# 214_oled_for_JetRacer.net
KiCad netlist of a schematic drawn in EAGLE
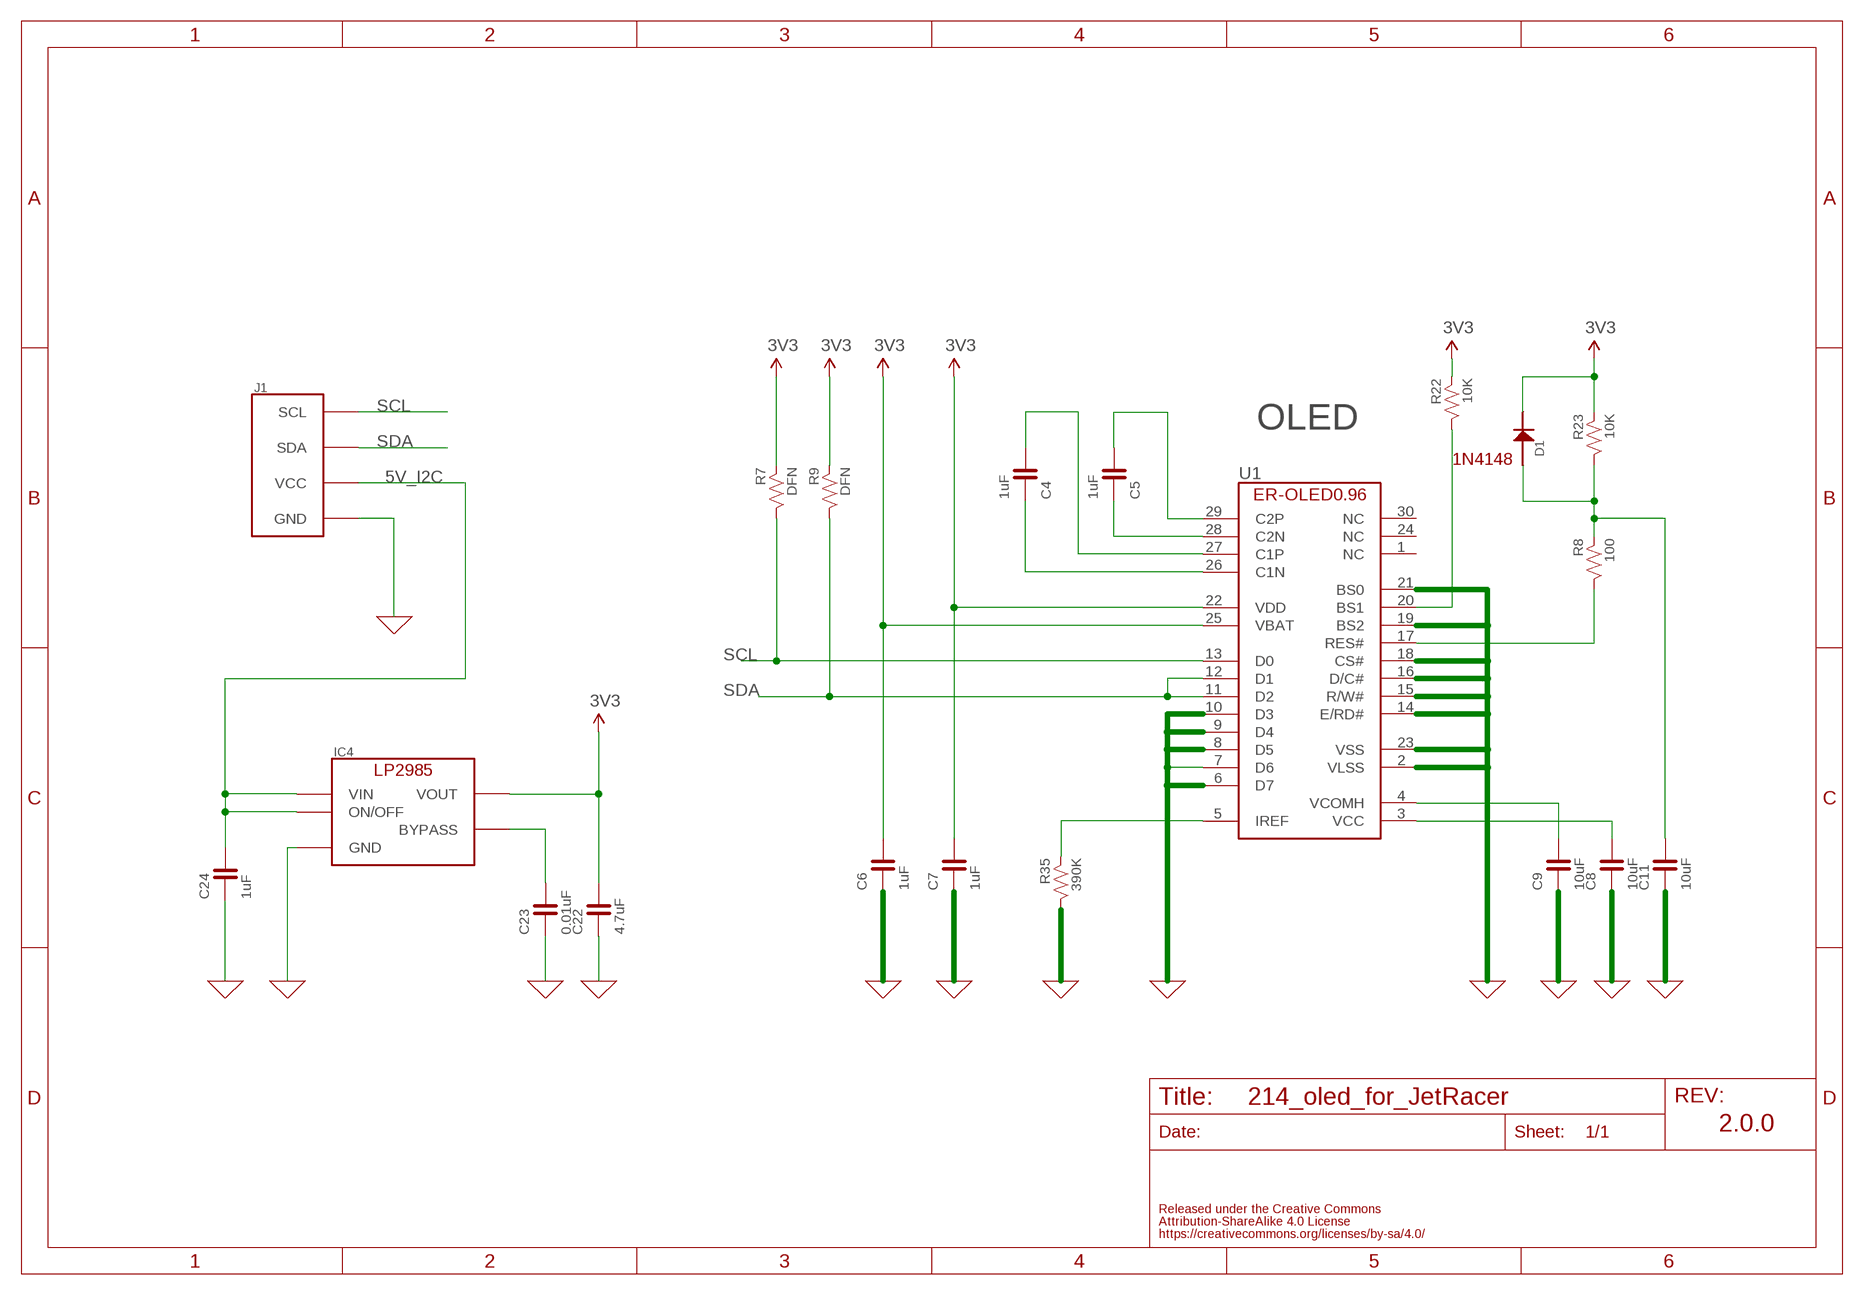
[diagram p0: schematic, sheet 1]

(export (version "E")
  (design (tool "Eeschema 10.0.6"))
  (components
    (comp (ref "C4")
      (value "1uF")
      (footprint "eagle-import:0603")
      (libsource (lib "eagle-import") (part "CAPACITOR-0603"))
    )
    (comp (ref "C5")
      (value "1uF")
      (footprint "eagle-import:0603")
      (libsource (lib "eagle-import") (part "CAPACITOR-0603"))
    )
    (comp (ref "C6")
      (value "1uF")
      (footprint "eagle-import:0603")
      (libsource (lib "eagle-import") (part "CAPACITOR-0603"))
    )
    (comp (ref "C7")
      (value "1uF")
      (footprint "eagle-import:0603")
      (libsource (lib "eagle-import") (part "CAPACITOR-0603"))
    )
    (comp (ref "C8")
      (value "10uF")
      (footprint "eagle-import:0603")
      (libsource (lib "eagle-import") (part "CAPACITOR-0603"))
    )
    (comp (ref "C9")
      (value "10uF")
      (footprint "eagle-import:0603")
      (libsource (lib "eagle-import") (part "CAPACITOR-0603"))
    )
    (comp (ref "C11")
      (value "10uF")
      (footprint "eagle-import:0603")
      (libsource (lib "eagle-import") (part "CAPACITOR-0603"))
    )
    (comp (ref "C22")
      (value "4.7uF")
      (footprint "eagle-import:0603")
      (libsource (lib "eagle-import") (part "CAPACITOR-0603"))
    )
    (comp (ref "C23")
      (value "0.01uF")
      (footprint "eagle-import:0603")
      (libsource (lib "eagle-import") (part "CAPACITOR-0603"))
    )
    (comp (ref "C24")
      (value "1uF")
      (footprint "eagle-import:0603")
      (libsource (lib "eagle-import") (part "CAPACITOR-0603"))
    )
    (comp (ref "D1")
      (value "1N4148")
      (footprint "eagle-import:1N4148W")
      (libsource (lib "eagle-import") (part "1N4148"))
    )
    (comp (ref "IC4")
      (value "LP2985-33DBV")
      (footprint "eagle-import:SOT-23-5")
      (libsource (lib "eagle-import") (part "LP2985-33DBV"))
    )
    (comp (ref "J1")
      (value "FABO_BRICK_I2C-S04B-PASK-2")
      (footprint "eagle-import:FABO_BRICK_I2C_S04B-PASK-2")
      (libsource (lib "eagle-import") (part "FABO_BRICK_I2C-S04B-PASK-2"))
    )
    (comp (ref "R7")
      (value "DFN")
      (footprint "eagle-import:0603")
      (libsource (lib "eagle-import") (part "RESISTOR-0603"))
    )
    (comp (ref "R8")
      (value "100")
      (footprint "eagle-import:0603")
      (libsource (lib "eagle-import") (part "RESISTOR-0603"))
    )
    (comp (ref "R9")
      (value "DFN")
      (footprint "eagle-import:0603")
      (libsource (lib "eagle-import") (part "RESISTOR-0603"))
    )
    (comp (ref "R22")
      (value "10K")
      (footprint "eagle-import:0603")
      (libsource (lib "eagle-import") (part "RESISTOR-0603"))
    )
    (comp (ref "R23")
      (value "10K")
      (footprint "eagle-import:0603")
      (libsource (lib "eagle-import") (part "RESISTOR-0603"))
    )
    (comp (ref "R35")
      (value "390K")
      (footprint "eagle-import:0603")
      (libsource (lib "eagle-import") (part "RESISTOR-0603"))
    )
    (comp (ref "U1")
      (value "ER-OLED0.96-1ER-CON30HT-1")
      (footprint "eagle-import:ER-CON30HT-1")
      (libsource (lib "eagle-import") (part "ER-OLED0.96-1ER-CON30HT-1"))
    )
  )
  (nets
    (net (code "1") (name "/5V_I2C") (class "Default")
      (node (ref "C24") (pin "2") (pinfunction "2_2") (pintype "passive"))
      (node (ref "IC4") (pin "1") (pinfunction "VIN_1") (pintype "input"))
      (node (ref "IC4") (pin "3") (pinfunction "ON/OFF_3") (pintype "input"))
      (node (ref "J1") (pin "VCC") (pinfunction "VCC_VCC") (pintype "bidirectional"))
    )
    (net (code "2") (name "/SCL") (class "Default")
      (node (ref "J1") (pin "SCL") (pinfunction "SCL_SCL") (pintype "bidirectional"))
      (node (ref "R7") (pin "2") (pinfunction "2_2") (pintype "bidirectional"))
      (node (ref "U1") (pin "13") (pinfunction "D0_13") (pintype "bidirectional"))
    )
    (net (code "3") (name "/SDA") (class "Default")
      (node (ref "J1") (pin "SDA") (pinfunction "SDA_SDA") (pintype "bidirectional"))
      (node (ref "R9") (pin "2") (pinfunction "2_2") (pintype "bidirectional"))
      (node (ref "U1") (pin "11") (pinfunction "D2_11") (pintype "bidirectional"))
      (node (ref "U1") (pin "12") (pinfunction "D1_12") (pintype "bidirectional"))
    )
    (net (code "4") (name "3V3") (class "Default")
      (node (ref "C22") (pin "2") (pinfunction "2_2") (pintype "passive"))
      (node (ref "C6") (pin "2") (pinfunction "2_2") (pintype "passive"))
      (node (ref "C7") (pin "2") (pinfunction "2_2") (pintype "passive"))
      (node (ref "D1") (pin "CATHODE") (pinfunction "CATHODE_CATHODE") (pintype "bidirectional"))
      (node (ref "IC4") (pin "5") (pinfunction "VOUT_5") (pintype "output"))
      (node (ref "R22") (pin "1") (pinfunction "1_1") (pintype "bidirectional"))
      (node (ref "R23") (pin "1") (pinfunction "1_1") (pintype "bidirectional"))
      (node (ref "R7") (pin "1") (pinfunction "1_1") (pintype "bidirectional"))
      (node (ref "R9") (pin "1") (pinfunction "1_1") (pintype "bidirectional"))
      (node (ref "U1") (pin "22") (pinfunction "VDD_22") (pintype "bidirectional"))
      (node (ref "U1") (pin "25") (pinfunction "VBAT_25") (pintype "bidirectional"))
    )
    (net (code "5") (name "GND") (class "Default")
      (node (ref "C11") (pin "1") (pinfunction "1_1") (pintype "passive"))
      (node (ref "C22") (pin "1") (pinfunction "1_1") (pintype "passive"))
      (node (ref "C23") (pin "1") (pinfunction "1_1") (pintype "passive"))
      (node (ref "C24") (pin "1") (pinfunction "1_1") (pintype "passive"))
      (node (ref "C6") (pin "1") (pinfunction "1_1") (pintype "passive"))
      (node (ref "C7") (pin "1") (pinfunction "1_1") (pintype "passive"))
      (node (ref "C8") (pin "1") (pinfunction "1_1") (pintype "passive"))
      (node (ref "C9") (pin "1") (pinfunction "1_1") (pintype "passive"))
      (node (ref "IC4") (pin "2") (pinfunction "GND_2") (pintype "power_in"))
      (node (ref "J1") (pin "GND") (pinfunction "GND_GND") (pintype "bidirectional"))
      (node (ref "R35") (pin "2") (pinfunction "2_2") (pintype "bidirectional"))
      (node (ref "U1") (pin "10") (pinfunction "D3_10") (pintype "bidirectional"))
      (node (ref "U1") (pin "14") (pinfunction "E/RD#_14") (pintype "bidirectional"))
      (node (ref "U1") (pin "15") (pinfunction "R/W#_15") (pintype "bidirectional"))
      (node (ref "U1") (pin "16") (pinfunction "D/C#_16") (pintype "bidirectional"))
      (node (ref "U1") (pin "18") (pinfunction "CS#_18") (pintype "bidirectional"))
      (node (ref "U1") (pin "19") (pinfunction "BS2_19") (pintype "bidirectional"))
      (node (ref "U1") (pin "2") (pinfunction "VLSS_2") (pintype "bidirectional"))
      (node (ref "U1") (pin "21") (pinfunction "BS0_21") (pintype "bidirectional"))
      (node (ref "U1") (pin "23") (pinfunction "VSS_23") (pintype "bidirectional"))
      (node (ref "U1") (pin "6") (pinfunction "D7_6") (pintype "bidirectional"))
      (node (ref "U1") (pin "7") (pinfunction "D6_7") (pintype "bidirectional"))
      (node (ref "U1") (pin "8") (pinfunction "D5_8") (pintype "bidirectional"))
      (node (ref "U1") (pin "9") (pinfunction "D4_9") (pintype "bidirectional"))
    )
    (net (code "6") (name "Net-(C11-Pad2)") (class "Default")
      (node (ref "C11") (pin "2") (pinfunction "2_2") (pintype "passive"))
      (node (ref "D1") (pin "ANODE") (pinfunction "ANODE_ANODE") (pintype "bidirectional"))
      (node (ref "R23") (pin "2") (pinfunction "2_2") (pintype "bidirectional"))
      (node (ref "R8") (pin "1") (pinfunction "1_1") (pintype "bidirectional"))
    )
    (net (code "7") (name "Net-(IC4-BYPASS)") (class "Default")
      (node (ref "C23") (pin "2") (pinfunction "2_2") (pintype "passive"))
      (node (ref "IC4") (pin "4") (pinfunction "BYPASS_4") (pintype "bidirectional"))
    )
    (net (code "8") (name "Net-(U1-BS1)") (class "Default")
      (node (ref "R22") (pin "2") (pinfunction "2_2") (pintype "bidirectional"))
      (node (ref "U1") (pin "20") (pinfunction "BS1_20") (pintype "bidirectional"))
    )
    (net (code "9") (name "Net-(U1-C1N)") (class "Default")
      (node (ref "C4") (pin "1") (pinfunction "1_1") (pintype "passive"))
      (node (ref "U1") (pin "26") (pinfunction "C1N_26") (pintype "bidirectional"))
    )
    (net (code "10") (name "Net-(U1-C1P)") (class "Default")
      (node (ref "C4") (pin "2") (pinfunction "2_2") (pintype "passive"))
      (node (ref "U1") (pin "27") (pinfunction "C1P_27") (pintype "bidirectional"))
    )
    (net (code "11") (name "Net-(U1-C2N)") (class "Default")
      (node (ref "C5") (pin "1") (pinfunction "1_1") (pintype "passive"))
      (node (ref "U1") (pin "28") (pinfunction "C2N_28") (pintype "bidirectional"))
    )
    (net (code "12") (name "Net-(U1-C2P)") (class "Default")
      (node (ref "C5") (pin "2") (pinfunction "2_2") (pintype "passive"))
      (node (ref "U1") (pin "29") (pinfunction "C2P_29") (pintype "bidirectional"))
    )
    (net (code "13") (name "Net-(U1-IREF)") (class "Default")
      (node (ref "R35") (pin "1") (pinfunction "1_1") (pintype "bidirectional"))
      (node (ref "U1") (pin "5") (pinfunction "IREF_5") (pintype "bidirectional"))
    )
    (net (code "14") (name "Net-(U1-RES#)") (class "Default")
      (node (ref "R8") (pin "2") (pinfunction "2_2") (pintype "bidirectional"))
      (node (ref "U1") (pin "17") (pinfunction "RES#_17") (pintype "bidirectional"))
    )
    (net (code "15") (name "Net-(U1-VCC)") (class "Default")
      (node (ref "C8") (pin "2") (pinfunction "2_2") (pintype "passive"))
      (node (ref "U1") (pin "3") (pinfunction "VCC_3") (pintype "bidirectional"))
    )
    (net (code "16") (name "Net-(U1-VCOMH)") (class "Default")
      (node (ref "C9") (pin "2") (pinfunction "2_2") (pintype "passive"))
      (node (ref "U1") (pin "4") (pinfunction "VCOMH_4") (pintype "bidirectional"))
    )
    (net (code "17") (name "unconnected-(U1-NC-Pad1)") (class "Default")
      (node (ref "U1") (pin "1") (pinfunction "NC_1") (pintype "bidirectional"))
    )
    (net (code "18") (name "unconnected-(U1-NC-Pad24)") (class "Default")
      (node (ref "U1") (pin "24") (pinfunction "NC_24") (pintype "bidirectional"))
    )
    (net (code "19") (name "unconnected-(U1-NC-Pad30)") (class "Default")
      (node (ref "U1") (pin "30") (pinfunction "NC_30") (pintype "bidirectional"))
    )
  )
)
